# ME433_HW2_2.net
KiCad netlist of a schematic drawn in EAGLE
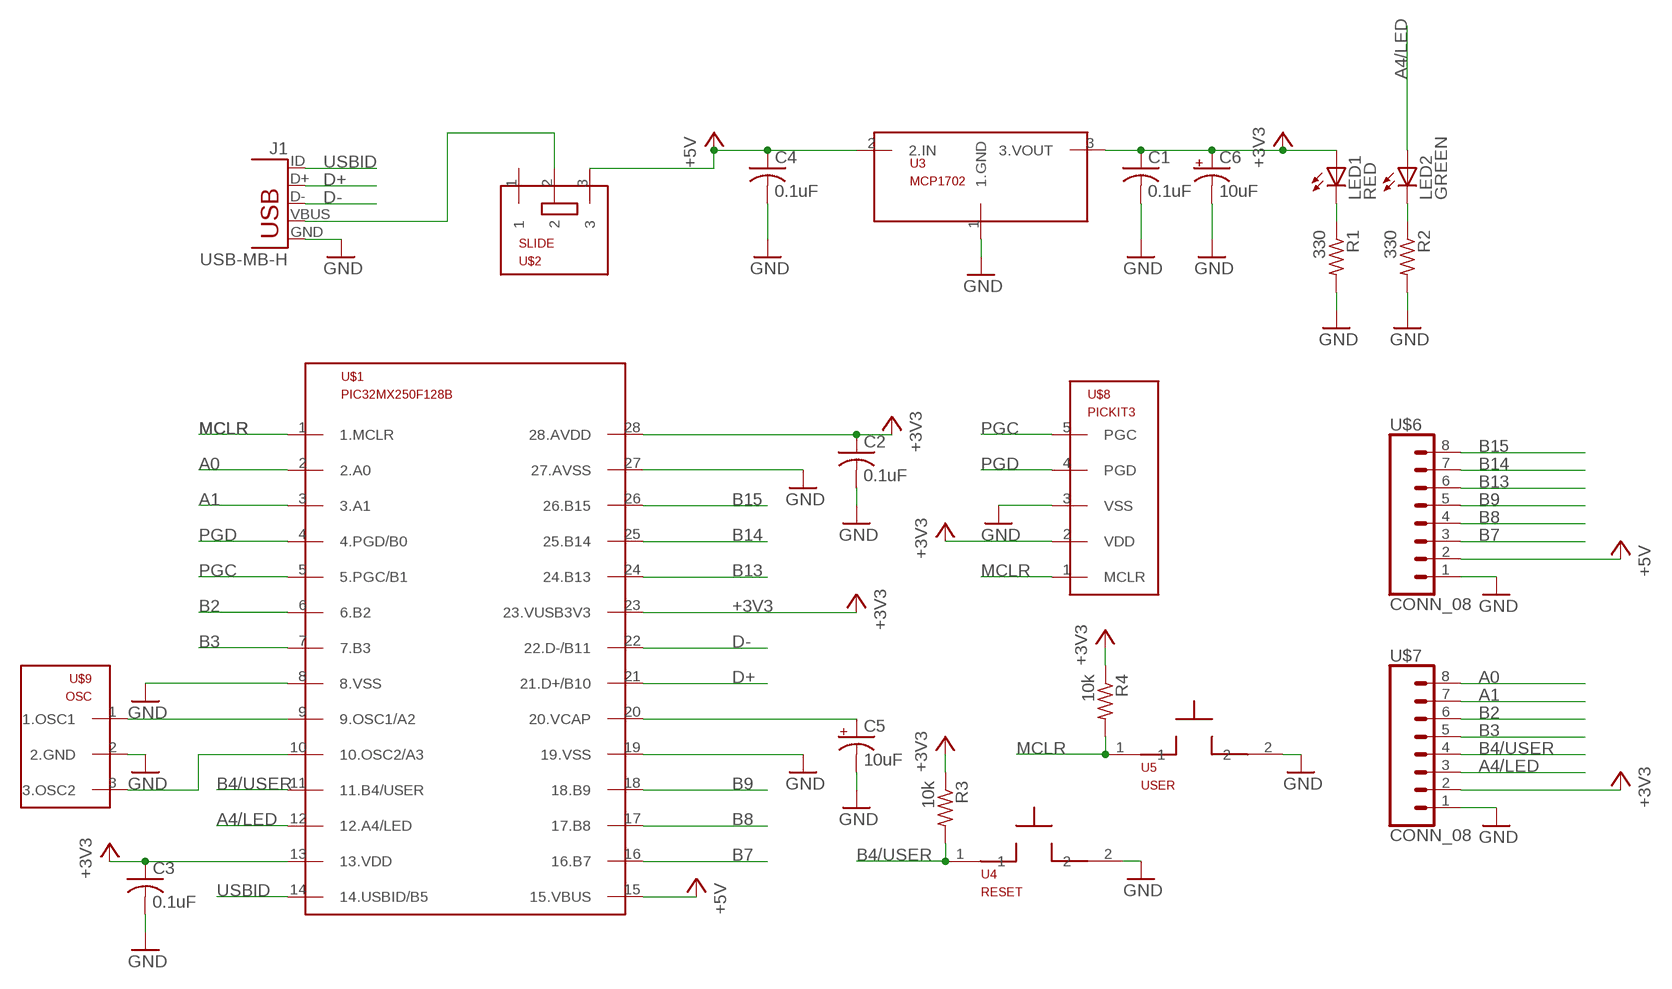
[diagram p0: schematic, sheet 1]

(export (version "E")
  (design (tool "Eeschema 10.0.6"))
  (components
    (comp (ref "C1")
      (value "0.1uF")
      (footprint "eagle-import:C025-025X050")
      (libsource (lib "eagle-import") (part "C-US025-025X050"))
    )
    (comp (ref "C2")
      (value "0.1uF")
      (footprint "eagle-import:C025-025X050")
      (libsource (lib "eagle-import") (part "C-US025-025X050"))
    )
    (comp (ref "C3")
      (value "0.1uF")
      (footprint "eagle-import:C025-025X050")
      (libsource (lib "eagle-import") (part "C-US025-025X050"))
    )
    (comp (ref "C4")
      (value "0.1uF")
      (footprint "eagle-import:C025-025X050")
      (libsource (lib "eagle-import") (part "C-US025-025X050"))
    )
    (comp (ref "C5")
      (value "10uF")
      (footprint "eagle-import:B45181B")
      (libsource (lib "eagle-import") (part "CPOL-USB45181B"))
    )
    (comp (ref "C6")
      (value "10uF")
      (footprint "eagle-import:B45181B")
      (libsource (lib "eagle-import") (part "CPOL-USB45181B"))
    )
    (comp (ref "J1")
      (value "USB-MB-H")
      (footprint "eagle-import:USB-MB-H")
      (libsource (lib "eagle-import") (part "USB-MB-H"))
    )
    (comp (ref "LED1")
      (value "RED")
      (footprint "eagle-import:LED3MM")
      (libsource (lib "eagle-import") (part "LED3MM"))
    )
    (comp (ref "LED2")
      (value "GREEN")
      (footprint "eagle-import:LED3MM")
      (libsource (lib "eagle-import") (part "LED3MM"))
    )
    (comp (ref "R1")
      (value "330")
      (footprint "eagle-import:0207_10")
      (libsource (lib "eagle-import") (part "R-US_0207/10"))
    )
    (comp (ref "R2")
      (value "330")
      (footprint "eagle-import:0207_10")
      (libsource (lib "eagle-import") (part "R-US_0207/10"))
    )
    (comp (ref "R3")
      (value "10k")
      (footprint "eagle-import:0207_10")
      (libsource (lib "eagle-import") (part "R-US_0207/10"))
    )
    (comp (ref "R4")
      (value "10k")
      (footprint "eagle-import:0207_10")
      (libsource (lib "eagle-import") (part "R-US_0207/10"))
    )
    (comp (ref "U$1")
      (value "PIC32MX250F128B")
      (footprint "eagle-import:DIL28-3")
      (libsource (lib "eagle-import") (part "PIC32MX250F128B"))
    )
    (comp (ref "U$2")
      (value "SLIDE")
      (footprint "eagle-import:SLIDE")
      (libsource (lib "eagle-import") (part "SLIDE"))
    )
    (comp (ref "U$6")
      (value "CONN_08")
      (footprint "eagle-import:1X08")
      (libsource (lib "eagle-import") (part "CONN_08"))
    )
    (comp (ref "U$7")
      (value "CONN_08")
      (footprint "eagle-import:1X08")
      (libsource (lib "eagle-import") (part "CONN_08"))
    )
    (comp (ref "U$8")
      (value "PICKIT3")
      (footprint "eagle-import:1X05")
      (libsource (lib "eagle-import") (part "PICKIT3"))
    )
    (comp (ref "U$9")
      (value "OSC")
      (footprint "eagle-import:OSC")
      (libsource (lib "eagle-import") (part "OSC"))
    )
    (comp (ref "U3")
      (value "MCP1702")
      (footprint "eagle-import:TO92")
      (libsource (lib "eagle-import") (part "MCP1702"))
    )
    (comp (ref "U4")
      (value "RESET")
      (footprint "eagle-import:PB")
      (libsource (lib "eagle-import") (part "PB"))
    )
    (comp (ref "U5")
      (value "USER")
      (footprint "eagle-import:PB")
      (libsource (lib "eagle-import") (part "PB"))
    )
  )
  (nets
    (net (code "1") (name "+3V3") (class "Default")
      (node (ref "C1") (pin "1") (pinfunction "1_1") (pintype "passive"))
      (node (ref "C2") (pin "1") (pinfunction "1_1") (pintype "passive"))
      (node (ref "C3") (pin "1") (pinfunction "1_1") (pintype "passive"))
      (node (ref "C6") (pin "+") (pinfunction "+_+") (pintype "passive"))
      (node (ref "LED1") (pin "A") (pinfunction "A_A") (pintype "passive"))
      (node (ref "R3") (pin "1") (pinfunction "1_1") (pintype "passive"))
      (node (ref "R4") (pin "1") (pinfunction "1_1") (pintype "passive"))
      (node (ref "U$1") (pin "13") (pinfunction "13.VDD_13") (pintype "bidirectional"))
      (node (ref "U$1") (pin "23") (pinfunction "23.VUSB3V3_23") (pintype "bidirectional"))
      (node (ref "U$1") (pin "28") (pinfunction "28.AVDD_28") (pintype "bidirectional"))
      (node (ref "U$7") (pin "2") (pinfunction "2_2") (pintype "passive"))
      (node (ref "U$8") (pin "2") (pinfunction "VDD_2") (pintype "bidirectional"))
      (node (ref "U3") (pin "3") (pinfunction "3.VOUT_3") (pintype "bidirectional"))
    )
    (net (code "2") (name "+5V") (class "Default")
      (node (ref "C4") (pin "1") (pinfunction "1_1") (pintype "passive"))
      (node (ref "U$1") (pin "15") (pinfunction "15.VBUS_15") (pintype "bidirectional"))
      (node (ref "U$2") (pin "3") (pinfunction "3_3") (pintype "bidirectional"))
      (node (ref "U$6") (pin "2") (pinfunction "2_2") (pintype "passive"))
      (node (ref "U3") (pin "2") (pinfunction "2.IN_2") (pintype "bidirectional"))
    )
    (net (code "3") (name "/A0") (class "Default")
      (node (ref "U$1") (pin "2") (pinfunction "2.A0_2") (pintype "bidirectional"))
      (node (ref "U$7") (pin "8") (pinfunction "8_8") (pintype "passive"))
    )
    (net (code "4") (name "/A1") (class "Default")
      (node (ref "U$1") (pin "3") (pinfunction "3.A1_3") (pintype "bidirectional"))
      (node (ref "U$7") (pin "7") (pinfunction "7_7") (pintype "passive"))
    )
    (net (code "5") (name "/A4{slash}LED") (class "Default")
      (node (ref "LED2") (pin "A") (pinfunction "A_A") (pintype "passive"))
      (node (ref "U$1") (pin "12") (pinfunction "12.A4/LED_12") (pintype "bidirectional"))
      (node (ref "U$7") (pin "3") (pinfunction "3_3") (pintype "passive"))
    )
    (net (code "6") (name "/B2") (class "Default")
      (node (ref "U$1") (pin "6") (pinfunction "6.B2_6") (pintype "bidirectional"))
      (node (ref "U$7") (pin "6") (pinfunction "6_6") (pintype "passive"))
    )
    (net (code "7") (name "/B3") (class "Default")
      (node (ref "U$1") (pin "7") (pinfunction "7.B3_7") (pintype "bidirectional"))
      (node (ref "U$7") (pin "5") (pinfunction "5_5") (pintype "passive"))
    )
    (net (code "8") (name "/B4{slash}USER") (class "Default")
      (node (ref "R3") (pin "2") (pinfunction "2_2") (pintype "passive"))
      (node (ref "U$1") (pin "11") (pinfunction "11.B4/USER_11") (pintype "bidirectional"))
      (node (ref "U$7") (pin "4") (pinfunction "4_4") (pintype "passive"))
      (node (ref "U4") (pin "1") (pinfunction "1_1") (pintype "bidirectional"))
    )
    (net (code "9") (name "/B7") (class "Default")
      (node (ref "U$1") (pin "16") (pinfunction "16.B7_16") (pintype "bidirectional"))
      (node (ref "U$6") (pin "3") (pinfunction "3_3") (pintype "passive"))
    )
    (net (code "10") (name "/B8") (class "Default")
      (node (ref "U$1") (pin "17") (pinfunction "17.B8_17") (pintype "bidirectional"))
      (node (ref "U$6") (pin "4") (pinfunction "4_4") (pintype "passive"))
    )
    (net (code "11") (name "/B9") (class "Default")
      (node (ref "U$1") (pin "18") (pinfunction "18.B9_18") (pintype "bidirectional"))
      (node (ref "U$6") (pin "5") (pinfunction "5_5") (pintype "passive"))
    )
    (net (code "12") (name "/B13") (class "Default")
      (node (ref "U$1") (pin "24") (pinfunction "24.B13_24") (pintype "bidirectional"))
      (node (ref "U$6") (pin "6") (pinfunction "6_6") (pintype "passive"))
    )
    (net (code "13") (name "/B14") (class "Default")
      (node (ref "U$1") (pin "25") (pinfunction "25.B14_25") (pintype "bidirectional"))
      (node (ref "U$6") (pin "7") (pinfunction "7_7") (pintype "passive"))
    )
    (net (code "14") (name "/B15") (class "Default")
      (node (ref "U$1") (pin "26") (pinfunction "26.B15_26") (pintype "bidirectional"))
      (node (ref "U$6") (pin "8") (pinfunction "8_8") (pintype "passive"))
    )
    (net (code "15") (name "/D+") (class "Default")
      (node (ref "J1") (pin "D+") (pinfunction "D+_D+") (pintype "bidirectional"))
      (node (ref "U$1") (pin "21") (pinfunction "21.D+/B10_21") (pintype "bidirectional"))
    )
    (net (code "16") (name "/D-") (class "Default")
      (node (ref "J1") (pin "D-") (pinfunction "D-_D-") (pintype "bidirectional"))
      (node (ref "U$1") (pin "22") (pinfunction "22.D-/B11_22") (pintype "bidirectional"))
    )
    (net (code "17") (name "/MCLR") (class "Default")
      (node (ref "R4") (pin "2") (pinfunction "2_2") (pintype "passive"))
      (node (ref "U$1") (pin "1") (pinfunction "1.MCLR_1") (pintype "bidirectional"))
      (node (ref "U$8") (pin "1") (pinfunction "MCLR_1") (pintype "bidirectional"))
      (node (ref "U5") (pin "1") (pinfunction "1_1") (pintype "bidirectional"))
    )
    (net (code "18") (name "/PGC") (class "Default")
      (node (ref "U$1") (pin "5") (pinfunction "5.PGC/B1_5") (pintype "bidirectional"))
      (node (ref "U$8") (pin "5") (pinfunction "PGC_5") (pintype "bidirectional"))
    )
    (net (code "19") (name "/PGD") (class "Default")
      (node (ref "U$1") (pin "4") (pinfunction "4.PGD/B0_4") (pintype "bidirectional"))
      (node (ref "U$8") (pin "4") (pinfunction "PGD_4") (pintype "bidirectional"))
    )
    (net (code "20") (name "/USBID") (class "Default")
      (node (ref "J1") (pin "ID") (pinfunction "ID_ID") (pintype "bidirectional"))
      (node (ref "U$1") (pin "14") (pinfunction "14.USBID/B5_14") (pintype "bidirectional"))
    )
    (net (code "21") (name "GND") (class "Default")
      (node (ref "C1") (pin "2") (pinfunction "2_2") (pintype "passive"))
      (node (ref "C2") (pin "2") (pinfunction "2_2") (pintype "passive"))
      (node (ref "C3") (pin "2") (pinfunction "2_2") (pintype "passive"))
      (node (ref "C4") (pin "2") (pinfunction "2_2") (pintype "passive"))
      (node (ref "C5") (pin "-") (pinfunction "-_-") (pintype "passive"))
      (node (ref "C6") (pin "-") (pinfunction "-_-") (pintype "passive"))
      (node (ref "J1") (pin "GND") (pinfunction "GND_GND") (pintype "bidirectional"))
      (node (ref "R1") (pin "2") (pinfunction "2_2") (pintype "passive"))
      (node (ref "R2") (pin "2") (pinfunction "2_2") (pintype "passive"))
      (node (ref "U$1") (pin "19") (pinfunction "19.VSS_19") (pintype "bidirectional"))
      (node (ref "U$1") (pin "27") (pinfunction "27.AVSS_27") (pintype "bidirectional"))
      (node (ref "U$1") (pin "8") (pinfunction "8.VSS_8") (pintype "bidirectional"))
      (node (ref "U$6") (pin "1") (pinfunction "1_1") (pintype "passive"))
      (node (ref "U$7") (pin "1") (pinfunction "1_1") (pintype "passive"))
      (node (ref "U$8") (pin "3") (pinfunction "VSS_3") (pintype "bidirectional"))
      (node (ref "U$9") (pin "2") (pinfunction "2.GND_2") (pintype "bidirectional"))
      (node (ref "U3") (pin "1") (pinfunction "1.GND_1") (pintype "bidirectional"))
      (node (ref "U4") (pin "2") (pinfunction "2_2") (pintype "bidirectional"))
      (node (ref "U5") (pin "2") (pinfunction "2_2") (pintype "bidirectional"))
    )
    (net (code "22") (name "Net-(J1-PadVBUS)") (class "Default")
      (node (ref "J1") (pin "VBUS") (pinfunction "VBUS_VBUS") (pintype "bidirectional"))
      (node (ref "U$2") (pin "2") (pinfunction "2_2") (pintype "bidirectional"))
    )
    (net (code "23") (name "Net-(LED1-C)") (class "Default")
      (node (ref "LED1") (pin "K") (pinfunction "C_K") (pintype "passive"))
      (node (ref "R1") (pin "1") (pinfunction "1_1") (pintype "passive"))
    )
    (net (code "24") (name "Net-(LED2-C)") (class "Default")
      (node (ref "LED2") (pin "K") (pinfunction "C_K") (pintype "passive"))
      (node (ref "R2") (pin "1") (pinfunction "1_1") (pintype "passive"))
    )
    (net (code "25") (name "Net-(U$1-9.OSC1{slash}A2)") (class "Default")
      (node (ref "U$1") (pin "9") (pinfunction "9.OSC1/A2_9") (pintype "bidirectional"))
      (node (ref "U$9") (pin "1") (pinfunction "1.OSC1_1") (pintype "bidirectional"))
    )
    (net (code "26") (name "Net-(U$1-10.OSC2{slash}A3)") (class "Default")
      (node (ref "U$1") (pin "10") (pinfunction "10.OSC2/A3_10") (pintype "bidirectional"))
      (node (ref "U$9") (pin "3") (pinfunction "3.OSC2_3") (pintype "bidirectional"))
    )
    (net (code "27") (name "Net-(U$1-20.VCAP)") (class "Default")
      (node (ref "C5") (pin "+") (pinfunction "+_+") (pintype "passive"))
      (node (ref "U$1") (pin "20") (pinfunction "20.VCAP_20") (pintype "bidirectional"))
    )
    (net (code "28") (name "unconnected-(U$2-Pad1)") (class "Default")
      (node (ref "U$2") (pin "1") (pinfunction "1_1") (pintype "bidirectional"))
    )
  )
)
